# attiny_rc_switch.net
KiCad netlist of a schematic drawn in EAGLE
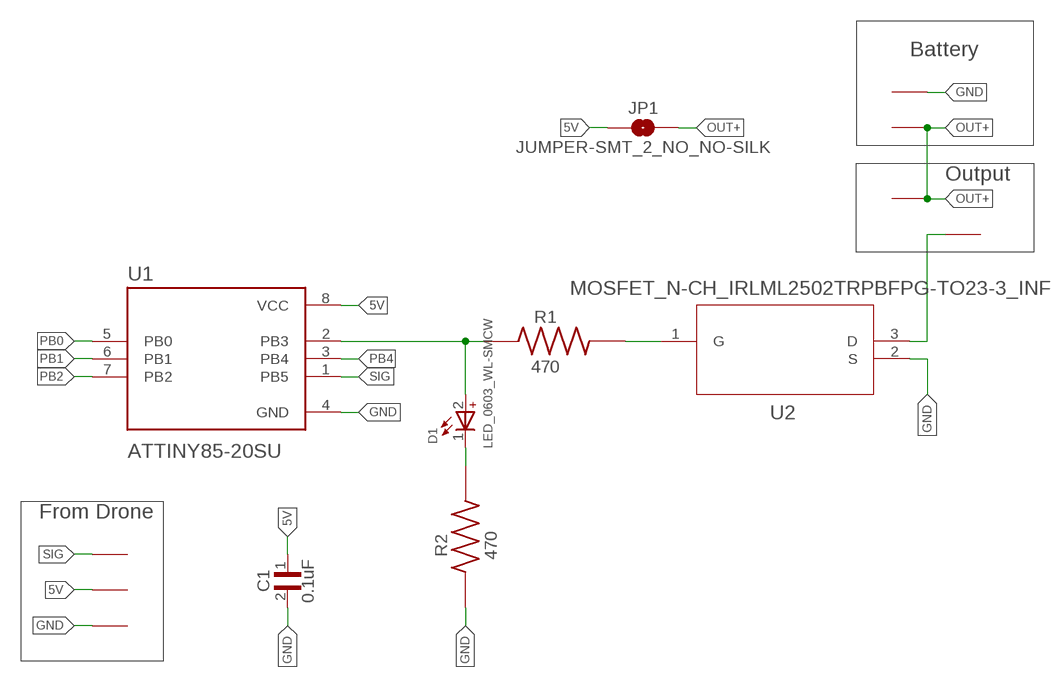
[diagram p0: schematic, sheet 1]

(export (version "E")
  (design (tool "Eeschema 10.0.6"))
  (components
    (comp (ref "C1")
      (value "0.1uF")
      (footprint "eagle-import:CC0603ZRY5V9BB")
      (libsource (lib "eagle-import") (part "CAPACITOR_CERAMIC_0603_50V_CC0603ZRY5V9BB"))
    )
    (comp (ref "D1")
      (value "LED_0603_WL-SMCW")
      (footprint "eagle-import:LED_0603_WL-SMCW")
      (libsource (lib "eagle-import") (part "LED_0603_WL-SMCW"))
    )
    (comp (ref "JP1")
      (value "JUMPER-SMT_2_NO_NO-SILK")
      (footprint "eagle-import:SMT-JUMPER_2_NO_NO-SILK")
      (libsource (lib "eagle-import") (part "JUMPER-SMT_2_NO_NO-SILK"))
    )
    (comp (ref "R1")
      (value "470")
      (footprint "eagle-import:RCS0603")
      (libsource (lib "eagle-import") (part "RESISTOR_0603_1/4W_RCS0603"))
    )
    (comp (ref "R2")
      (value "470")
      (footprint "eagle-import:RCS0603")
      (libsource (lib "eagle-import") (part "RESISTOR_0603_1/4W_RCS0603"))
    )
    (comp (ref "U$1")
      (value "SMD_PAD")
      (footprint "eagle-import:SMD_PAD")
      (libsource (lib "eagle-import") (part "SMD_PAD"))
    )
    (comp (ref "U$2")
      (value "SMD_PAD")
      (footprint "eagle-import:SMD_PAD")
      (libsource (lib "eagle-import") (part "SMD_PAD"))
    )
    (comp (ref "U$3")
      (value "SMD_PAD")
      (footprint "eagle-import:SMD_PAD")
      (libsource (lib "eagle-import") (part "SMD_PAD"))
    )
    (comp (ref "U$4")
      (value "SMD_PAD")
      (footprint "eagle-import:SMD_PAD")
      (libsource (lib "eagle-import") (part "SMD_PAD"))
    )
    (comp (ref "U$5")
      (value "SMD_PAD")
      (footprint "eagle-import:SMD_PAD")
      (libsource (lib "eagle-import") (part "SMD_PAD"))
    )
    (comp (ref "U$6")
      (value "SMD_PAD")
      (footprint "eagle-import:SMD_PAD")
      (libsource (lib "eagle-import") (part "SMD_PAD"))
    )
    (comp (ref "U$8")
      (value "SMD_PAD")
      (footprint "eagle-import:SMD_PAD")
      (libsource (lib "eagle-import") (part "SMD_PAD"))
    )
    (comp (ref "U1")
      (value "ATTINY85-20SU")
      (footprint "eagle-import:ATTINY85-20SU")
      (fields (field (name "MF") "Microchip Technology") (field (name "MP") "ATTINY85V-10SU"))
      (libsource (lib "eagle-import") (part "ATTINY85-20SU"))
    )
    (comp (ref "U2")
      (value "MOSFET_N-CH_IRLML2502TRPBFPG-TO23-3_INF")
      (footprint "eagle-import:MOSFET_N-CH_IRLML2502TRPBF")
      (fields
        (field (name "MANUFACTURER_PART_NUMBER") "IRLML2502TRPBF")
        (field (name "COPYRIGHT") "Copyright (C) 2024 Ultra Librarian. All rights reserved.")
      )
      (libsource (lib "eagle-import") (part "MOSFET_N-CH_IRLML2502TRPBFPG-TO23-3_INF"))
    )
  )
  (nets
    (net (code "1") (name "5V") (class "Default")
      (node (ref "C1") (pin "1") (pinfunction "1_1") (pintype "passive"))
      (node (ref "JP1") (pin "1") (pinfunction "1_1") (pintype "passive"))
      (node (ref "U$1") (pin "P$1") (pinfunction "P$1_P$1") (pintype "bidirectional"))
      (node (ref "U1") (pin "8") (pinfunction "VCC_8") (pintype "power_in"))
    )
    (net (code "2") (name "GND") (class "Default")
      (node (ref "C1") (pin "2") (pinfunction "2_2") (pintype "passive"))
      (node (ref "R2") (pin "1") (pinfunction "1_1") (pintype "passive"))
      (node (ref "U$2") (pin "P$1") (pinfunction "P$1_P$1") (pintype "bidirectional"))
      (node (ref "U$4") (pin "P$1") (pinfunction "P$1_P$1") (pintype "bidirectional"))
      (node (ref "U1") (pin "4") (pinfunction "GND_4") (pintype "power_in"))
      (node (ref "U2") (pin "2") (pinfunction "S_2") (pintype "passive"))
    )
    (net (code "3") (name "Net-(D1-+)") (class "Default")
      (node (ref "D1") (pin "2") (pinfunction "+_2") (pintype "passive"))
      (node (ref "R1") (pin "1") (pinfunction "1_1") (pintype "passive"))
      (node (ref "U1") (pin "2") (pinfunction "PB3_2") (pintype "bidirectional"))
    )
    (net (code "4") (name "Net-(D1--)") (class "Default")
      (node (ref "D1") (pin "1") (pinfunction "-_1") (pintype "passive"))
      (node (ref "R2") (pin "2") (pinfunction "2_2") (pintype "passive"))
    )
    (net (code "5") (name "Net-(U2-D)") (class "Default")
      (node (ref "U$6") (pin "P$1") (pinfunction "P$1_P$1") (pintype "bidirectional"))
      (node (ref "U2") (pin "3") (pinfunction "D_3") (pintype "passive"))
    )
    (net (code "6") (name "Net-(U2-G)") (class "Default")
      (node (ref "R1") (pin "2") (pinfunction "2_2") (pintype "passive"))
      (node (ref "U2") (pin "1") (pinfunction "G_1") (pintype "passive"))
    )
    (net (code "7") (name "OUT+") (class "Default")
      (node (ref "JP1") (pin "2") (pinfunction "2_2") (pintype "passive"))
      (node (ref "U$3") (pin "P$1") (pinfunction "P$1_P$1") (pintype "bidirectional"))
      (node (ref "U$5") (pin "P$1") (pinfunction "P$1_P$1") (pintype "bidirectional"))
    )
    (net (code "8") (name "PB0") (class "Default")
      (node (ref "U1") (pin "5") (pinfunction "PB0_5") (pintype "bidirectional"))
    )
    (net (code "9") (name "PB1") (class "Default")
      (node (ref "U1") (pin "6") (pinfunction "PB1_6") (pintype "bidirectional"))
    )
    (net (code "10") (name "PB2") (class "Default")
      (node (ref "U1") (pin "7") (pinfunction "PB2_7") (pintype "bidirectional"))
    )
    (net (code "11") (name "PB4") (class "Default")
      (node (ref "U1") (pin "3") (pinfunction "PB4_3") (pintype "bidirectional"))
    )
    (net (code "12") (name "SIG") (class "Default")
      (node (ref "U$8") (pin "P$1") (pinfunction "P$1_P$1") (pintype "bidirectional"))
      (node (ref "U1") (pin "1") (pinfunction "PB5_1") (pintype "bidirectional"))
    )
  )
)
